# FTDI.net
KiCad netlist of a schematic drawn in Altium Designer
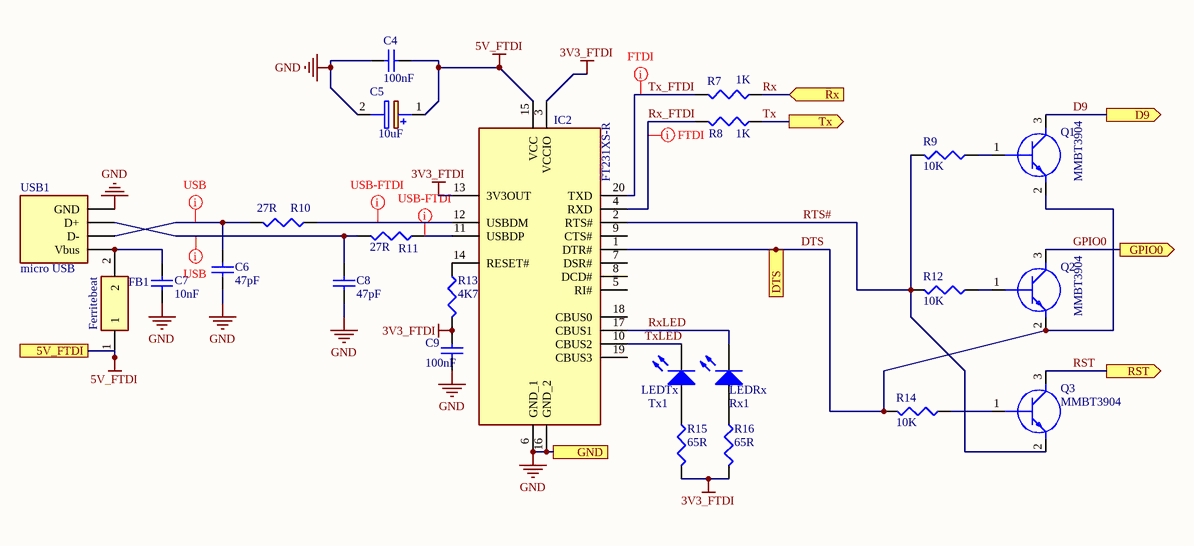
[diagram p0: FTDI.SchDoc]

(export (version "E")
  (design (tool "Eeschema 10.0.6"))
  (components
    (comp (ref "C4")
      (value "100nF")
      (footprint "1608[0603]")
      (description "Capacitor (Semiconductor SIM Model)")
      (fields (field (name "PUBLISHER") "Altium Limited"))
      (libsource (lib "Miscellaneous Devices") (part "Cap Semi"))
    )
    (comp (ref "C5")
      (value "10uF")
      (footprint "CAPPM3216X180N")
      (description "Capacitor Polarised")
      (fields
        (field (name "MANUFACTURER_PART_NUMBER") "TAJA106K004RNJ")
        (field (name "MOUSER PART NUMBER") "581-TAJA106K004R")
      )
      (libsource (lib "SamacSys") (part "TAJA106K004RNJ"))
    )
    (comp (ref "C6")
      (value "47pF")
      (footprint "1608[0603]")
      (description "Capacitor (Semiconductor SIM Model)")
      (fields (field (name "PUBLISHER") "Altium Limited"))
      (libsource (lib "Miscellaneous Devices") (part "Cap Semi"))
    )
    (comp (ref "C7")
      (value "10nF")
      (footprint "1608[0603]")
      (description "Capacitor (Semiconductor SIM Model)")
      (fields (field (name "PUBLISHER") "Altium Limited"))
      (libsource (lib "Miscellaneous Devices") (part "Cap Semi"))
    )
    (comp (ref "C8")
      (value "47pF")
      (footprint "1608[0603]")
      (description "Capacitor (Semiconductor SIM Model)")
      (fields (field (name "PUBLISHER") "Altium Limited"))
      (libsource (lib "Miscellaneous Devices") (part "Cap Semi"))
    )
    (comp (ref "C9")
      (value "100nF")
      (footprint "1608[0603]")
      (description "Capacitor (Semiconductor SIM Model)")
      (fields (field (name "PUBLISHER") "Altium Limited"))
      (libsource (lib "Miscellaneous Devices") (part "Cap Semi"))
    )
    (comp (ref "FB1")
      (value "Ferritebeat")
      (footprint "BEADC1608X95N")
      (description "Ferrite Bead")
      (fields
        (field (name "MANUFACTURER_PART_NUMBER") "BLM18DN151SH1D")
        (field (name "MOUSER PART NUMBER") "81-BLM18DN151SH1D")
      )
      (libsource (lib "SamacSys") (part "BLM18DN151SH1D"))
    )
    (comp (ref "IC2")
      (value "FT231XS-R")
      (footprint "SamacSys:SOP64P599X175-20N")
      (description "Integrated Circuit")
      (fields (field (name "MOUSER PART NUMBER") "895-FT231XS-R"))
      (libsource (lib "*") (part "FT231XS-R"))
    )
    (comp (ref "Q1")
      (value "MMBT3904")
      (footprint "SamacSys:SOT95P230X110-3N")
      (description "Transistor BJT NPN")
      (fields
        (field (name "MANUFACTURER_PART_NUMBER") "MMBT3904,215")
        (field (name "MOUSER PART NUMBER") "771-MMBT3904T/R")
      )
      (libsource (lib "*") (part "MMBT3904,215"))
    )
    (comp (ref "Q2")
      (value "MMBT3904")
      (footprint "SamacSys:SOT95P230X110-3N")
      (description "Transistor BJT NPN")
      (fields
        (field (name "MANUFACTURER_PART_NUMBER") "MMBT3904,215")
        (field (name "MOUSER PART NUMBER") "771-MMBT3904T/R")
      )
      (libsource (lib "*") (part "MMBT3904,215"))
    )
    (comp (ref "Q3")
      (value "MMBT3904")
      (footprint "SamacSys:SOT95P230X110-3N")
      (description "Transistor BJT NPN")
      (fields
        (field (name "MANUFACTURER_PART_NUMBER") "MMBT3904,215")
        (field (name "MOUSER PART NUMBER") "771-MMBT3904T/R")
      )
      (libsource (lib "*") (part "MMBT3904,215"))
    )
    (comp (ref "R7")
      (value "1K")
      (footprint "J1-0603")
      (description "Resistor")
      (fields (field (name "PUBLISHER") "Altium Limited"))
      (libsource (lib "Miscellaneous Devices") (part "Res3"))
    )
    (comp (ref "R8")
      (value "1K")
      (footprint "J1-0603")
      (description "Resistor")
      (fields (field (name "PUBLISHER") "Altium Limited"))
      (libsource (lib "Miscellaneous Devices") (part "Res3"))
    )
    (comp (ref "R9")
      (value "10K")
      (footprint "J1-0603")
      (description "Resistor")
      (fields (field (name "PUBLISHER") "Altium Limited"))
      (libsource (lib "Miscellaneous Devices") (part "Res3"))
    )
    (comp (ref "R10")
      (value "27R")
      (footprint "J1-0603")
      (description "Resistor")
      (fields (field (name "PUBLISHER") "Altium Limited"))
      (libsource (lib "Miscellaneous Devices") (part "Res3"))
    )
    (comp (ref "R11")
      (value "27R")
      (footprint "J1-0603")
      (description "Resistor")
      (fields (field (name "PUBLISHER") "Altium Limited"))
      (libsource (lib "Miscellaneous Devices") (part "Res3"))
    )
    (comp (ref "R12")
      (value "10K")
      (footprint "J1-0603")
      (description "Resistor")
      (fields (field (name "PUBLISHER") "Altium Limited"))
      (libsource (lib "Miscellaneous Devices") (part "Res3"))
    )
    (comp (ref "R13")
      (value "4K7")
      (footprint "J1-0603")
      (description "Resistor")
      (fields (field (name "PUBLISHER") "Altium Limited"))
      (libsource (lib "Miscellaneous Devices") (part "Res3"))
    )
    (comp (ref "R14")
      (value "10K")
      (footprint "J1-0603")
      (description "Resistor")
      (fields (field (name "PUBLISHER") "Altium Limited"))
      (libsource (lib "Miscellaneous Devices") (part "Res3"))
    )
    (comp (ref "R15")
      (value "65R")
      (footprint "J1-0603")
      (description "Resistor")
      (fields (field (name "PUBLISHER") "Altium Limited"))
      (libsource (lib "Miscellaneous Devices") (part "Res3"))
    )
    (comp (ref "R16")
      (value "65R")
      (footprint "J1-0603")
      (description "Resistor")
      (fields (field (name "PUBLISHER") "Altium Limited"))
      (libsource (lib "Miscellaneous Devices") (part "Res3"))
    )
    (comp (ref "Rx1")
      (value "LEDRx")
      (footprint "LED 0603")
      (description "Typical BLUE SiC LED")
      (fields (field (name "PUBLISHER") "Altium Limited"))
      (libsource (lib "Miscellaneous Devices") (part "LED3"))
    )
    (comp (ref "Tx1")
      (value "LEDTx")
      (footprint "LED 0603")
      (description "Typical BLUE SiC LED")
      (fields (field (name "PUBLISHER") "Altium Limited"))
      (libsource (lib "Miscellaneous Devices") (part "LED3"))
    )
    (comp (ref "USB1")
      (value "micro USB")
      (footprint "micro USB")
      (libsource (lib "SamacSys") (part "micro USB"))
    )
  )
  (nets
    (net (code "1") (name "/D9") (class "Default")
      (node (ref "Q1") (pin "3") (pinfunction "C_3") (pintype "passive"))
    )
    (net (code "2") (name "/DTS") (class "Default")
      (node (ref "IC2") (pin "1") (pinfunction "DTR#_1") (pintype "passive"))
      (node (ref "Q1") (pin "2") (pinfunction "E_2") (pintype "passive"))
      (node (ref "Q2") (pin "2") (pinfunction "E_2") (pintype "passive"))
      (node (ref "R14") (pin "2") (pinfunction "2_2") (pintype "passive"))
    )
    (net (code "3") (name "/GPIO0") (class "Default")
      (node (ref "Q2") (pin "3") (pinfunction "C_3") (pintype "passive"))
    )
    (net (code "4") (name "/RST") (class "Default")
      (node (ref "Q3") (pin "3") (pinfunction "C_3") (pintype "passive"))
    )
    (net (code "5") (name "/RTS#") (class "Default")
      (node (ref "IC2") (pin "2") (pinfunction "RTS#_2") (pintype "passive"))
      (node (ref "Q3") (pin "2") (pinfunction "E_2") (pintype "passive"))
      (node (ref "R12") (pin "2") (pinfunction "2_2") (pintype "passive"))
      (node (ref "R9") (pin "2") (pinfunction "2_2") (pintype "passive"))
    )
    (net (code "6") (name "/Rx") (class "Default")
      (node (ref "R7") (pin "1") (pinfunction "1_1") (pintype "passive"))
    )
    (net (code "7") (name "/RxLED") (class "Default")
      (node (ref "IC2") (pin "17") (pinfunction "CBUS1_17") (pintype "passive"))
      (node (ref "Rx1") (pin "2") (pinfunction "K_2") (pintype "passive"))
    )
    (net (code "8") (name "/Rx_FTDI") (class "Default")
      (node (ref "IC2") (pin "4") (pinfunction "RXD_4") (pintype "passive"))
      (node (ref "R8") (pin "2") (pinfunction "2_2") (pintype "passive"))
    )
    (net (code "9") (name "/Tx") (class "Default")
      (node (ref "R8") (pin "1") (pinfunction "1_1") (pintype "passive"))
    )
    (net (code "10") (name "/TxLED") (class "Default")
      (node (ref "IC2") (pin "10") (pinfunction "CBUS2_10") (pintype "passive"))
      (node (ref "Tx1") (pin "2") (pinfunction "K_2") (pintype "passive"))
    )
    (net (code "11") (name "/Tx_FTDI") (class "Default")
      (node (ref "IC2") (pin "20") (pinfunction "TXD_20") (pintype "passive"))
      (node (ref "R7") (pin "2") (pinfunction "2_2") (pintype "passive"))
    )
    (net (code "12") (name "3V3_FTDI") (class "Default")
      (node (ref "C9") (pin "1") (pinfunction "1_1") (pintype "passive"))
      (node (ref "IC2") (pin "13") (pinfunction "3V3OUT_13") (pintype "passive"))
      (node (ref "IC2") (pin "3") (pinfunction "VCCIO_3") (pintype "passive"))
      (node (ref "R13") (pin "2") (pinfunction "2_2") (pintype "passive"))
      (node (ref "R15") (pin "2") (pinfunction "2_2") (pintype "passive"))
      (node (ref "R16") (pin "2") (pinfunction "2_2") (pintype "passive"))
    )
    (net (code "13") (name "5V_FTDI") (class "Default")
      (node (ref "C4") (pin "2") (pinfunction "2_2") (pintype "passive"))
      (node (ref "C5") (pin "1") (pinfunction "+_1") (pintype "passive"))
      (node (ref "FB1") (pin "1") (pinfunction "1_1") (pintype "passive"))
      (node (ref "IC2") (pin "15") (pinfunction "VCC_15") (pintype "passive"))
    )
    (net (code "14") (name "GND") (class "Default")
      (node (ref "C4") (pin "1") (pinfunction "1_1") (pintype "passive"))
      (node (ref "C5") (pin "2") (pinfunction "-_2") (pintype "passive"))
      (node (ref "C6") (pin "2") (pinfunction "2_2") (pintype "passive"))
      (node (ref "C7") (pin "1") (pinfunction "1_1") (pintype "passive"))
      (node (ref "C8") (pin "2") (pinfunction "2_2") (pintype "passive"))
      (node (ref "C9") (pin "2") (pinfunction "2_2") (pintype "passive"))
      (node (ref "IC2") (pin "16") (pinfunction "GND_2_16") (pintype "passive"))
      (node (ref "IC2") (pin "6") (pinfunction "GND_1_6") (pintype "passive"))
      (node (ref "USB1") (pin "5") (pinfunction "GND_5") (pintype "passive"))
    )
    (net (code "15") (name "Net-(IC2-RESET#)") (class "Default")
      (node (ref "IC2") (pin "14") (pinfunction "RESET#_14") (pintype "passive"))
      (node (ref "R13") (pin "1") (pinfunction "1_1") (pintype "passive"))
    )
    (net (code "16") (name "Net-(IC2-USBDM)") (class "Default")
      (node (ref "IC2") (pin "12") (pinfunction "USBDM_12") (pintype "passive"))
      (node (ref "R10") (pin "1") (pinfunction "1_1") (pintype "passive"))
    )
    (net (code "17") (name "Net-(IC2-USBDP)") (class "Default")
      (node (ref "IC2") (pin "11") (pinfunction "USBDP_11") (pintype "passive"))
      (node (ref "R11") (pin "1") (pinfunction "1_1") (pintype "passive"))
    )
    (net (code "18") (name "Net-(Q1-B)") (class "Default")
      (node (ref "Q1") (pin "1") (pinfunction "B_1") (pintype "passive"))
      (node (ref "R9") (pin "1") (pinfunction "1_1") (pintype "passive"))
    )
    (net (code "19") (name "Net-(Q2-B)") (class "Default")
      (node (ref "Q2") (pin "1") (pinfunction "B_1") (pintype "passive"))
      (node (ref "R12") (pin "1") (pinfunction "1_1") (pintype "passive"))
    )
    (net (code "20") (name "Net-(Q3-B)") (class "Default")
      (node (ref "Q3") (pin "1") (pinfunction "B_1") (pintype "passive"))
      (node (ref "R14") (pin "1") (pinfunction "1_1") (pintype "passive"))
    )
    (net (code "21") (name "Net-(Rx1-A)") (class "Default")
      (node (ref "R16") (pin "1") (pinfunction "1_1") (pintype "passive"))
      (node (ref "Rx1") (pin "1") (pinfunction "A_1") (pintype "passive"))
    )
    (net (code "22") (name "Net-(Tx1-A)") (class "Default")
      (node (ref "R15") (pin "1") (pinfunction "1_1") (pintype "passive"))
      (node (ref "Tx1") (pin "1") (pinfunction "A_1") (pintype "passive"))
    )
    (net (code "23") (name "Net-(USB1-D+)") (class "Default")
      (node (ref "C8") (pin "1") (pinfunction "1_1") (pintype "passive"))
      (node (ref "R11") (pin "2") (pinfunction "2_2") (pintype "passive"))
      (node (ref "USB1") (pin "3") (pinfunction "D+_3") (pintype "passive"))
    )
    (net (code "24") (name "Net-(USB1-D-)") (class "Default")
      (node (ref "C6") (pin "1") (pinfunction "1_1") (pintype "passive"))
      (node (ref "R10") (pin "2") (pinfunction "2_2") (pintype "passive"))
      (node (ref "USB1") (pin "2") (pinfunction "D-_2") (pintype "passive"))
    )
    (net (code "25") (name "Net-(USB1-Vbus)") (class "Default")
      (node (ref "C7") (pin "2") (pinfunction "2_2") (pintype "passive"))
      (node (ref "FB1") (pin "2") (pinfunction "2_2") (pintype "passive"))
      (node (ref "USB1") (pin "1") (pinfunction "Vbus_1") (pintype "passive"))
    )
    (net (code "26") (name "unconnected-(IC2-CBUS0-Pad18)") (class "Default")
      (node (ref "IC2") (pin "18") (pinfunction "CBUS0_18") (pintype "passive"))
    )
    (net (code "27") (name "unconnected-(IC2-CBUS3-Pad19)") (class "Default")
      (node (ref "IC2") (pin "19") (pinfunction "CBUS3_19") (pintype "passive"))
    )
    (net (code "28") (name "unconnected-(IC2-CTS#-Pad9)") (class "Default")
      (node (ref "IC2") (pin "9") (pinfunction "CTS#_9") (pintype "passive"))
    )
    (net (code "29") (name "unconnected-(IC2-DCD#-Pad8)") (class "Default")
      (node (ref "IC2") (pin "8") (pinfunction "DCD#_8") (pintype "passive"))
    )
    (net (code "30") (name "unconnected-(IC2-DSR#-Pad7)") (class "Default")
      (node (ref "IC2") (pin "7") (pinfunction "DSR#_7") (pintype "passive"))
    )
    (net (code "31") (name "unconnected-(IC2-RI#-Pad5)") (class "Default")
      (node (ref "IC2") (pin "5") (pinfunction "RI#_5") (pintype "passive"))
    )
  )
)
